# leddriver.net
KiCad netlist of a schematic drawn in EAGLE
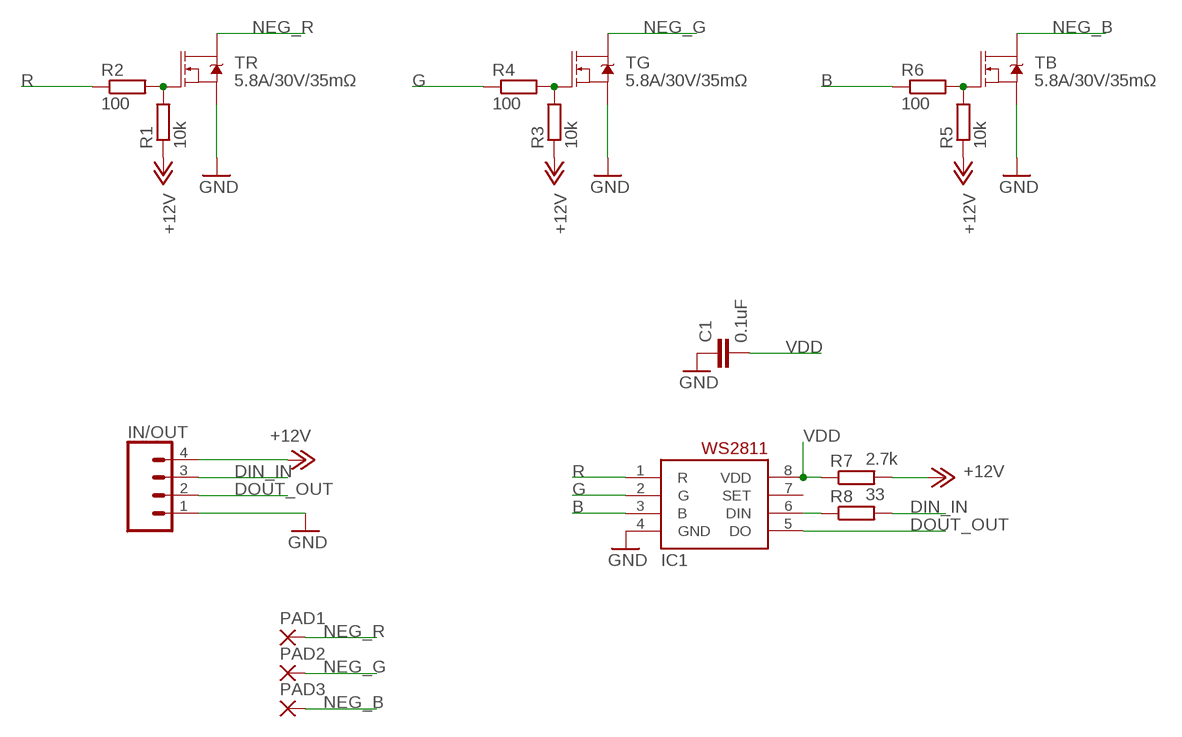
[diagram p0: schematic, sheet 1]

(export (version "E")
  (design (tool "Eeschema 10.0.6"))
  (components
    (comp (ref "C1")
      (value "0.1uF")
      (footprint "eagle-import:C1206")
      (libsource (lib "eagle-import") (part "C-EUC1206"))
    )
    (comp (ref "IC1")
      (value "WS2811-SOP8")
      (footprint "eagle-import:SO08-SKINNYPADS")
      (libsource (lib "eagle-import") (part "WS2811-SOP8"))
    )
    (comp (ref "IN/OUT")
      (value "CONN_04LONGPADS")
      (footprint "eagle-import:1X04_LONGPADS")
      (libsource (lib "eagle-import") (part "CONN_04LONGPADS"))
    )
    (comp (ref "PAD1")
      (value "3,81/1,4")
      (footprint "eagle-import:3,81_1,4")
      (libsource (lib "eagle-import") (part "3,81/1,4"))
    )
    (comp (ref "PAD2")
      (value "3,81/1,4")
      (footprint "eagle-import:3,81_1,4")
      (libsource (lib "eagle-import") (part "3,81/1,4"))
    )
    (comp (ref "PAD3")
      (value "3,81/1,4")
      (footprint "eagle-import:3,81_1,4")
      (libsource (lib "eagle-import") (part "3,81/1,4"))
    )
    (comp (ref "R1")
      (value "10k")
      (footprint "eagle-import:R0805")
      (libsource (lib "eagle-import") (part "R-EU_R0805"))
    )
    (comp (ref "R2")
      (value "100")
      (footprint "eagle-import:R0805")
      (libsource (lib "eagle-import") (part "R-EU_R0805"))
    )
    (comp (ref "R3")
      (value "10k")
      (footprint "eagle-import:R0805")
      (libsource (lib "eagle-import") (part "R-EU_R0805"))
    )
    (comp (ref "R4")
      (value "100")
      (footprint "eagle-import:R0805")
      (libsource (lib "eagle-import") (part "R-EU_R0805"))
    )
    (comp (ref "R5")
      (value "10k")
      (footprint "eagle-import:R0805")
      (libsource (lib "eagle-import") (part "R-EU_R0805"))
    )
    (comp (ref "R6")
      (value "100")
      (footprint "eagle-import:R0805")
      (libsource (lib "eagle-import") (part "R-EU_R0805"))
    )
    (comp (ref "R7")
      (value "2.7k")
      (footprint "eagle-import:R0805")
      (libsource (lib "eagle-import") (part "R-EU_R0805"))
    )
    (comp (ref "R8")
      (value "33")
      (footprint "eagle-import:R0805")
      (libsource (lib "eagle-import") (part "R-EU_R0805"))
    )
    (comp (ref "TB")
      (value "5.8A/30V/35mΩ")
      (footprint "eagle-import:SOT23-3")
      (libsource (lib "eagle-import") (part "MOSFET-NCH-AO3404A"))
    )
    (comp (ref "TG")
      (value "5.8A/30V/35mΩ")
      (footprint "eagle-import:SOT23-3")
      (libsource (lib "eagle-import") (part "MOSFET-NCH-AO3404A"))
    )
    (comp (ref "TR")
      (value "5.8A/30V/35mΩ")
      (footprint "eagle-import:SOT23-3")
      (libsource (lib "eagle-import") (part "MOSFET-NCH-AO3404A"))
    )
  )
  (nets
    (net (code "1") (name "+12V") (class "Default")
      (node (ref "IN/OUT") (pin "4") (pinfunction "4_4") (pintype "passive"))
      (node (ref "R1") (pin "1") (pinfunction "1_1") (pintype "passive"))
      (node (ref "R3") (pin "1") (pinfunction "1_1") (pintype "passive"))
      (node (ref "R5") (pin "1") (pinfunction "1_1") (pintype "passive"))
      (node (ref "R7") (pin "2") (pinfunction "2_2") (pintype "passive"))
    )
    (net (code "2") (name "/B") (class "Default")
      (node (ref "IC1") (pin "3") (pinfunction "B_3") (pintype "open_collector"))
      (node (ref "R6") (pin "1") (pinfunction "1_1") (pintype "passive"))
    )
    (net (code "3") (name "/DIN_IN") (class "Default")
      (node (ref "IN/OUT") (pin "3") (pinfunction "3_3") (pintype "passive"))
      (node (ref "R8") (pin "2") (pinfunction "2_2") (pintype "passive"))
    )
    (net (code "4") (name "/DOUT_OUT") (class "Default")
      (node (ref "IC1") (pin "5") (pinfunction "DO_5") (pintype "output"))
      (node (ref "IN/OUT") (pin "2") (pinfunction "2_2") (pintype "passive"))
    )
    (net (code "5") (name "/G") (class "Default")
      (node (ref "IC1") (pin "2") (pinfunction "G_2") (pintype "open_collector"))
      (node (ref "R4") (pin "1") (pinfunction "1_1") (pintype "passive"))
    )
    (net (code "6") (name "/NEG_B") (class "Default")
      (node (ref "PAD3") (pin "1") (pinfunction "P_1") (pintype "passive"))
      (node (ref "TB") (pin "3") (pinfunction "D_3") (pintype "bidirectional"))
    )
    (net (code "7") (name "/NEG_G") (class "Default")
      (node (ref "PAD2") (pin "1") (pinfunction "P_1") (pintype "passive"))
      (node (ref "TG") (pin "3") (pinfunction "D_3") (pintype "bidirectional"))
    )
    (net (code "8") (name "/NEG_R") (class "Default")
      (node (ref "PAD1") (pin "1") (pinfunction "P_1") (pintype "passive"))
      (node (ref "TR") (pin "3") (pinfunction "D_3") (pintype "bidirectional"))
    )
    (net (code "9") (name "/R") (class "Default")
      (node (ref "IC1") (pin "1") (pinfunction "R_1") (pintype "open_collector"))
      (node (ref "R2") (pin "1") (pinfunction "1_1") (pintype "passive"))
    )
    (net (code "10") (name "/VDD") (class "Default")
      (node (ref "C1") (pin "2") (pinfunction "2_2") (pintype "passive"))
      (node (ref "IC1") (pin "8") (pinfunction "VDD_8") (pintype "power_in"))
      (node (ref "R7") (pin "1") (pinfunction "1_1") (pintype "passive"))
    )
    (net (code "11") (name "GND") (class "Default")
      (node (ref "C1") (pin "1") (pinfunction "1_1") (pintype "passive"))
      (node (ref "IC1") (pin "4") (pinfunction "GND_4") (pintype "power_in"))
      (node (ref "IN/OUT") (pin "1") (pinfunction "1_1") (pintype "passive"))
      (node (ref "TB") (pin "2") (pinfunction "S_2") (pintype "bidirectional"))
      (node (ref "TG") (pin "2") (pinfunction "S_2") (pintype "bidirectional"))
      (node (ref "TR") (pin "2") (pinfunction "S_2") (pintype "bidirectional"))
    )
    (net (code "12") (name "Net-(IC1-DIN)") (class "Default")
      (node (ref "IC1") (pin "6") (pinfunction "DIN_6") (pintype "input"))
      (node (ref "R8") (pin "1") (pinfunction "1_1") (pintype "passive"))
    )
    (net (code "13") (name "Net-(TB-G)") (class "Default")
      (node (ref "R5") (pin "2") (pinfunction "2_2") (pintype "passive"))
      (node (ref "R6") (pin "2") (pinfunction "2_2") (pintype "passive"))
      (node (ref "TB") (pin "1") (pinfunction "G_1") (pintype "bidirectional"))
    )
    (net (code "14") (name "Net-(TG-G)") (class "Default")
      (node (ref "R3") (pin "2") (pinfunction "2_2") (pintype "passive"))
      (node (ref "R4") (pin "2") (pinfunction "2_2") (pintype "passive"))
      (node (ref "TG") (pin "1") (pinfunction "G_1") (pintype "bidirectional"))
    )
    (net (code "15") (name "Net-(TR-G)") (class "Default")
      (node (ref "R1") (pin "2") (pinfunction "2_2") (pintype "passive"))
      (node (ref "R2") (pin "2") (pinfunction "2_2") (pintype "passive"))
      (node (ref "TR") (pin "1") (pinfunction "G_1") (pintype "bidirectional"))
    )
    (net (code "16") (name "unconnected-(IC1-SET-Pad7)") (class "Default")
      (node (ref "IC1") (pin "7") (pinfunction "SET_7") (pintype "input"))
    )
  )
)
